# Pixeled_Proto-A0.net
KiCad netlist of a schematic drawn in EAGLE
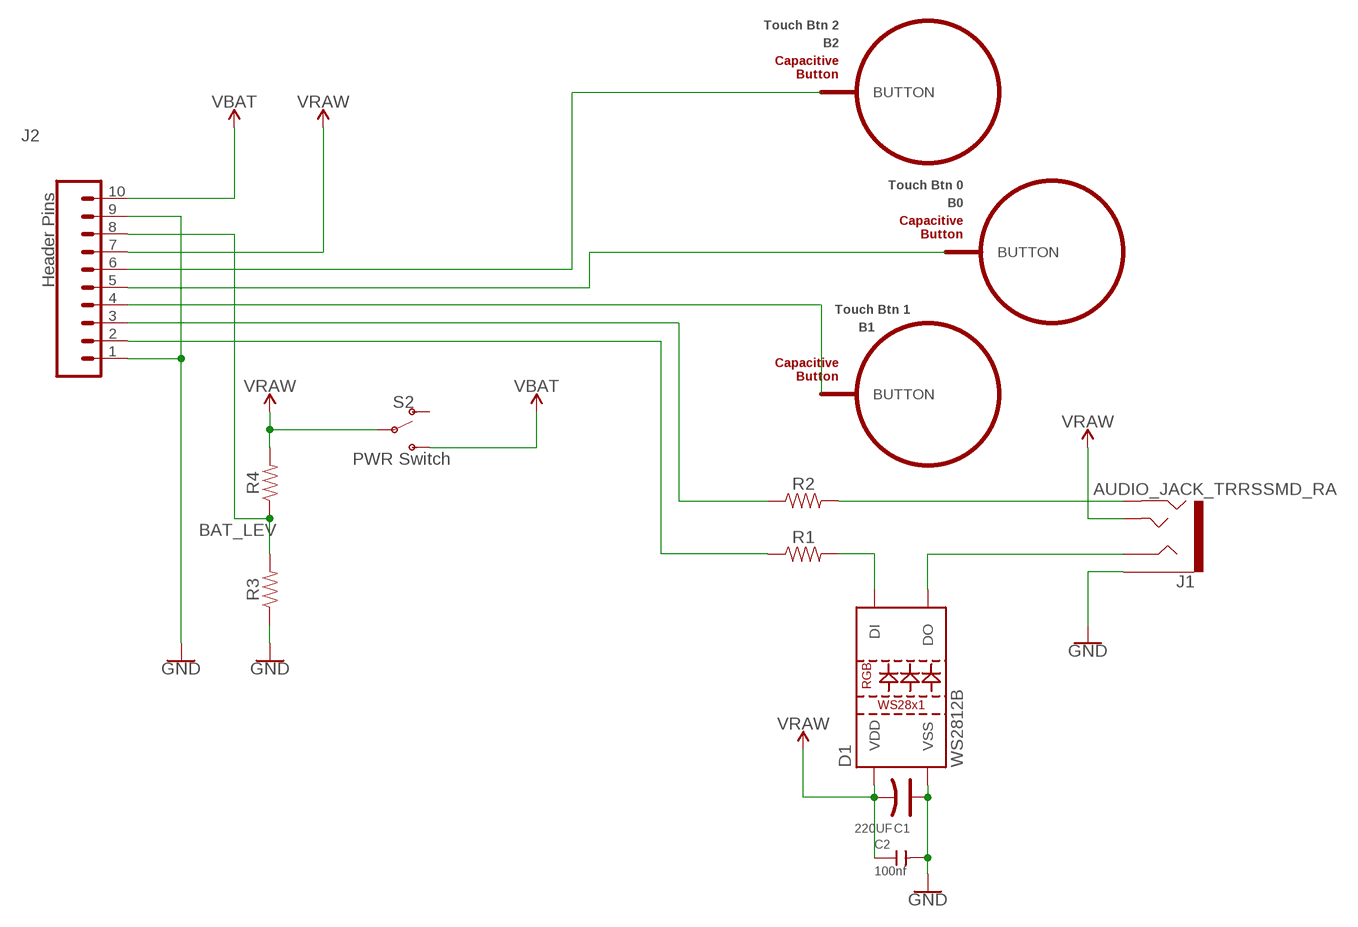
[diagram p0: schematic, sheet 1]

(export (version "E")
  (design (tool "Eeschema 10.0.6"))
  (components
    (comp (ref "B0")
      (value "Touch Btn 0")
      (footprint "eagle-import:BUTTON_PASSIVE_8MM")
      (libsource (lib "eagle-import") (part "BUTTON_PASSIVE8MM"))
    )
    (comp (ref "B1")
      (value "Touch Btn 1")
      (footprint "eagle-import:BUTTON_PASSIVE_12MM")
      (libsource (lib "eagle-import") (part "BUTTON_PASSIVE12MM"))
    )
    (comp (ref "B2")
      (value "Touch Btn 2")
      (footprint "eagle-import:BUTTON_PASSIVE_12MM")
      (libsource (lib "eagle-import") (part "BUTTON_PASSIVE12MM"))
    )
    (comp (ref "C1")
      (value "220UF")
      (footprint "eagle-import:ELECTRO-SMD-C-6MM")
      (fields (field (name "MPN") "CS1E221M-CRE77"))
      (libsource (lib "eagle-import") (part "ALUMINUM-SMD-220UF-16V(D6.3-H7.7MM)"))
    )
    (comp (ref "C2")
      (value "100nf")
      (footprint "eagle-import:C0805")
      (fields (field (name "MPN") "CC0805KRX7R9BB104"))
      (libsource (lib "eagle-import") (part "CERAMIC-100NF-50V-10%-X7R(0805)"))
    )
    (comp (ref "D1")
      (value "WS2812B")
      (footprint "eagle-import:WS2812B")
      (libsource (lib "eagle-import") (part "WS2812B"))
    )
    (comp (ref "J1")
      (value "AUDIO_JACK_TRRSSMD_RA")
      (footprint "eagle-import:AUDIO_JACK_3.5MM_TRRS_SMD_RA")
      (libsource (lib "eagle-import") (part "AUDIO_JACK_TRRSSMD_RA"))
    )
    (comp (ref "J2")
      (value "Header Pins")
      (footprint "eagle-import:1X10")
      (libsource (lib "eagle-import") (part "CONN_10{dblquote}"))
    )
    (comp (ref "R1")
      (value "RESISTOR0805")
      (footprint "eagle-import:0805")
      (libsource (lib "eagle-import") (part "RESISTOR0805"))
    )
    (comp (ref "R2")
      (value "RESISTOR0805")
      (footprint "eagle-import:0805")
      (libsource (lib "eagle-import") (part "RESISTOR0805"))
    )
    (comp (ref "R3")
      (value "RESISTOR0805")
      (footprint "eagle-import:0805")
      (libsource (lib "eagle-import") (part "RESISTOR0805"))
    )
    (comp (ref "R4")
      (value "RESISTOR0805")
      (footprint "eagle-import:0805")
      (libsource (lib "eagle-import") (part "RESISTOR0805"))
    )
    (comp (ref "S2")
      (value "PWR Switch")
      (footprint "eagle-import:SWITCH_SPST_SMD_A")
      (libsource (lib "eagle-import") (part "SWITCH-SPDT-SMD-RIGHT-ANGLE"))
    )
  )
  (nets
    (net (code "1") (name "/BAT_LEV") (class "Default")
      (node (ref "J2") (pin "8") (pinfunction "8_8") (pintype "passive"))
      (node (ref "R3") (pin "2") (pinfunction "2_2") (pintype "passive"))
      (node (ref "R4") (pin "1") (pinfunction "1_1") (pintype "passive"))
    )
    (net (code "2") (name "GND") (class "Default")
      (node (ref "C1") (pin "+") (pinfunction "+_+") (pintype "passive"))
      (node (ref "C2") (pin "2") (pinfunction "2_2") (pintype "passive"))
      (node (ref "D1") (pin "3") (pinfunction "VSS_3") (pintype "bidirectional"))
      (node (ref "J1") (pin "EARTH") (pinfunction "EARTH_EARTH") (pintype "bidirectional"))
      (node (ref "J2") (pin "1") (pinfunction "1_1") (pintype "passive"))
      (node (ref "J2") (pin "9") (pinfunction "9_9") (pintype "passive"))
      (node (ref "R3") (pin "1") (pinfunction "1_1") (pintype "passive"))
    )
    (net (code "3") (name "Net-(B0-PadBUTTON)") (class "Default")
      (node (ref "B0") (pin "BUTTON") (pinfunction "BUTTON_BUTTON") (pintype "passive"))
      (node (ref "J2") (pin "5") (pinfunction "5_5") (pintype "passive"))
    )
    (net (code "4") (name "Net-(B1-PadBUTTON)") (class "Default")
      (node (ref "B1") (pin "BUTTON") (pinfunction "BUTTON_BUTTON") (pintype "passive"))
      (node (ref "J2") (pin "4") (pinfunction "4_4") (pintype "passive"))
    )
    (net (code "5") (name "Net-(B2-PadBUTTON)") (class "Default")
      (node (ref "B2") (pin "BUTTON") (pinfunction "BUTTON_BUTTON") (pintype "passive"))
      (node (ref "J2") (pin "6") (pinfunction "6_6") (pintype "passive"))
    )
    (net (code "6") (name "Net-(D1-DI)") (class "Default")
      (node (ref "D1") (pin "4") (pinfunction "DI_4") (pintype "bidirectional"))
      (node (ref "R1") (pin "2") (pinfunction "2_2") (pintype "passive"))
    )
    (net (code "7") (name "Net-(D1-DO)") (class "Default")
      (node (ref "D1") (pin "2") (pinfunction "DO_2") (pintype "bidirectional"))
      (node (ref "J1") (pin "RING1") (pinfunction "RING1_RING1") (pintype "bidirectional"))
    )
    (net (code "8") (name "Net-(J1-PadRING2)") (class "Default")
      (node (ref "J1") (pin "RING2") (pinfunction "RING2_RING2") (pintype "bidirectional"))
      (node (ref "R2") (pin "2") (pinfunction "2_2") (pintype "passive"))
    )
    (net (code "9") (name "Net-(J2-Pad2)") (class "Default")
      (node (ref "J2") (pin "2") (pinfunction "2_2") (pintype "passive"))
      (node (ref "R1") (pin "1") (pinfunction "1_1") (pintype "passive"))
    )
    (net (code "10") (name "Net-(J2-Pad3)") (class "Default")
      (node (ref "J2") (pin "3") (pinfunction "3_3") (pintype "passive"))
      (node (ref "R2") (pin "1") (pinfunction "1_1") (pintype "passive"))
    )
    (net (code "11") (name "VBAT") (class "Default")
      (node (ref "J2") (pin "10") (pinfunction "10_10") (pintype "passive"))
      (node (ref "S2") (pin "3") (pinfunction "S_3") (pintype "passive"))
    )
    (net (code "12") (name "VRAW") (class "Default")
      (node (ref "C1") (pin "-") (pinfunction "-_-") (pintype "passive"))
      (node (ref "C2") (pin "1") (pinfunction "1_1") (pintype "passive"))
      (node (ref "D1") (pin "1") (pinfunction "VDD_1") (pintype "bidirectional"))
      (node (ref "J1") (pin "TIP") (pinfunction "TIP_TIP") (pintype "bidirectional"))
      (node (ref "J2") (pin "7") (pinfunction "7_7") (pintype "passive"))
      (node (ref "R4") (pin "2") (pinfunction "2_2") (pintype "passive"))
      (node (ref "S2") (pin "2") (pinfunction "P_2") (pintype "passive"))
    )
    (net (code "13") (name "unconnected-(S2-O-Pad1)") (class "Default")
      (node (ref "S2") (pin "1") (pinfunction "O_1") (pintype "passive"))
    )
  )
)
